# IoT_2015.net
KiCad netlist of a schematic drawn in EAGLE
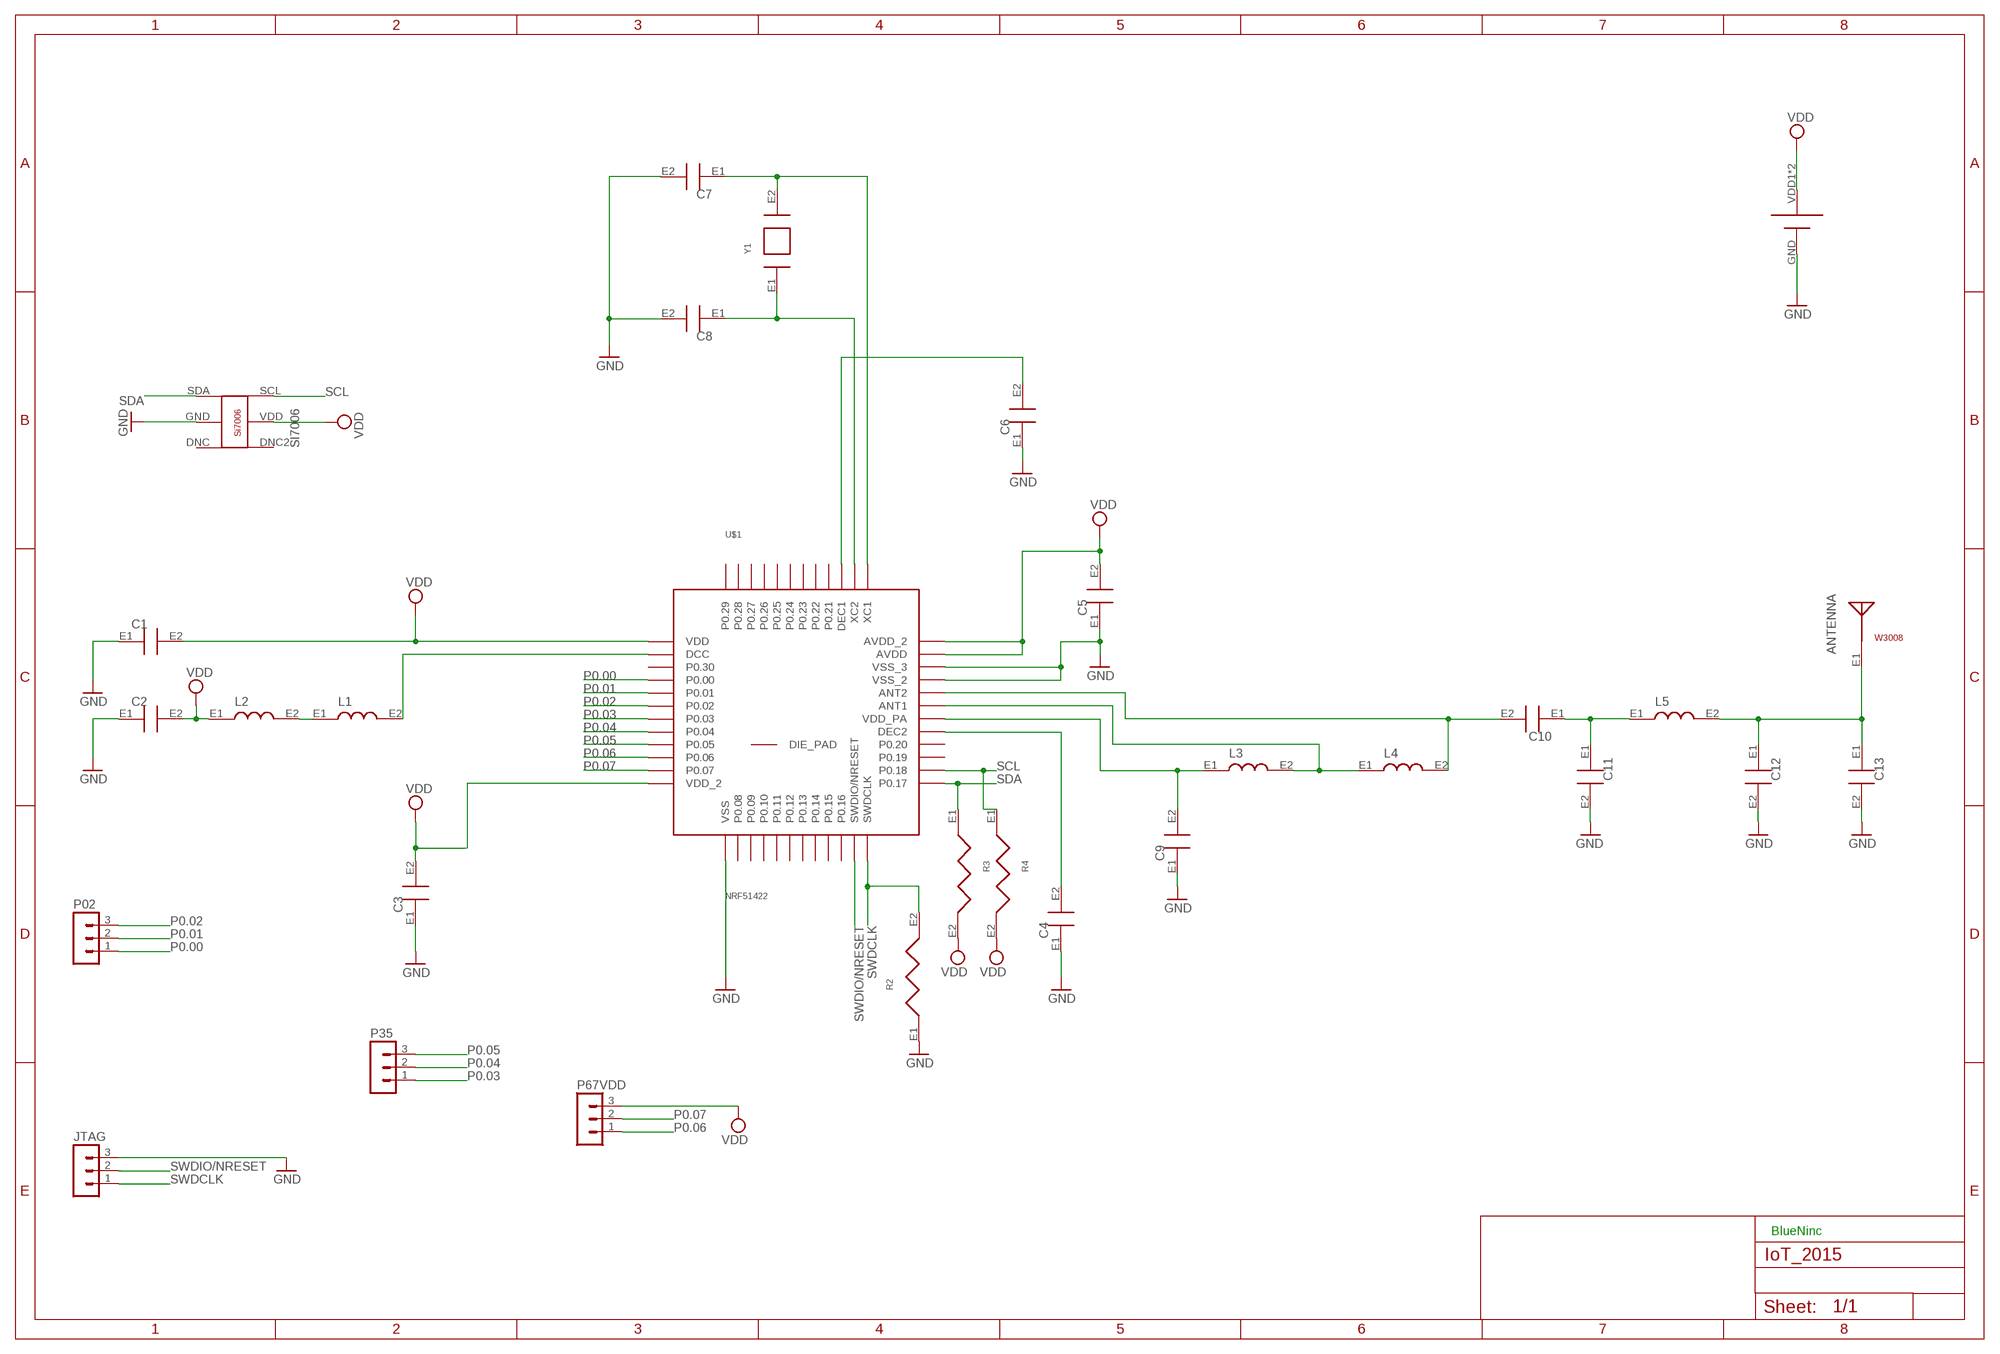
[diagram p0: schematic, sheet 1]

(export (version "E")
  (design (tool "Eeschema 10.0.6"))
  (components
    (comp (ref "ANTENNA")
      (value "W3008")
      (footprint "eagle-import:W3008")
      (libsource (lib "eagle-import") (part "W3008"))
    )
    (comp (ref "BATTERY")
      (value "BAT-HLD-001")
      (footprint "eagle-import:BAT-HLD-001")
      (libsource (lib "eagle-import") (part "BAT-HLD-001"))
    )
    (comp (ref "C1")
      (value "VJ1603_W1BC")
      (footprint "eagle-import:VJ1603_W1BC")
      (libsource (lib "eagle-import") (part "VJ1603_W1BC"))
    )
    (comp (ref "C2")
      (value "VJ1603_W1BC")
      (footprint "eagle-import:VJ1603_W1BC")
      (libsource (lib "eagle-import") (part "VJ1603_W1BC"))
    )
    (comp (ref "C3")
      (value "VJ1603_W1BC")
      (footprint "eagle-import:VJ1603_W1BC")
      (libsource (lib "eagle-import") (part "VJ1603_W1BC"))
    )
    (comp (ref "C4")
      (value "VJ1603_W1BC")
      (footprint "eagle-import:VJ1603_W1BC")
      (libsource (lib "eagle-import") (part "VJ1603_W1BC"))
    )
    (comp (ref "C5")
      (value "VJ1603_W1BC")
      (footprint "eagle-import:VJ1603_W1BC")
      (libsource (lib "eagle-import") (part "VJ1603_W1BC"))
    )
    (comp (ref "C6")
      (value "VJ1603_W1BC")
      (footprint "eagle-import:VJ1603_W1BC")
      (libsource (lib "eagle-import") (part "VJ1603_W1BC"))
    )
    (comp (ref "C7")
      (value "VJ1603_W1BC")
      (footprint "eagle-import:VJ1603_W1BC")
      (libsource (lib "eagle-import") (part "VJ1603_W1BC"))
    )
    (comp (ref "C8")
      (value "VJ1603_W1BC")
      (footprint "eagle-import:VJ1603_W1BC")
      (libsource (lib "eagle-import") (part "VJ1603_W1BC"))
    )
    (comp (ref "C9")
      (value "VJ1603_W1BC")
      (footprint "eagle-import:VJ1603_W1BC")
      (libsource (lib "eagle-import") (part "VJ1603_W1BC"))
    )
    (comp (ref "C10")
      (value "VJ1603_W1BC")
      (footprint "eagle-import:VJ1603_W1BC")
      (libsource (lib "eagle-import") (part "VJ1603_W1BC"))
    )
    (comp (ref "C11")
      (value "VJ1603_W1BC")
      (footprint "eagle-import:VJ1603_W1BC")
      (libsource (lib "eagle-import") (part "VJ1603_W1BC"))
    )
    (comp (ref "C12")
      (value "VJ1603_W1BC")
      (footprint "eagle-import:VJ1603_W1BC")
      (libsource (lib "eagle-import") (part "VJ1603_W1BC"))
    )
    (comp (ref "C13")
      (value "VJ1603_W1BC")
      (footprint "eagle-import:VJ1603_W1BC")
      (libsource (lib "eagle-import") (part "VJ1603_W1BC"))
    )
    (comp (ref "JTAG")
      (value "MA03-1")
      (footprint "eagle-import:MA03-1")
      (libsource (lib "eagle-import") (part "MA03-1"))
    )
    (comp (ref "L1")
      (value "JTI_CAT_2012_INDUCTORS_CHIP-242427")
      (footprint "eagle-import:JTI_CAT_2012_INDUCTORS_CHIP-242427")
      (libsource (lib "eagle-import") (part "JTI_CAT_2012_INDUCTORS_CHIP-242427"))
    )
    (comp (ref "L2")
      (value "JTI_CAT_2012_INDUCTORS_CHIP-242427")
      (footprint "eagle-import:JTI_CAT_2012_INDUCTORS_CHIP-242427")
      (libsource (lib "eagle-import") (part "JTI_CAT_2012_INDUCTORS_CHIP-242427"))
    )
    (comp (ref "L3")
      (value "JTI_CAT_2012_INDUCTORS_CHIP-242427")
      (footprint "eagle-import:JTI_CAT_2012_INDUCTORS_CHIP-242427")
      (libsource (lib "eagle-import") (part "JTI_CAT_2012_INDUCTORS_CHIP-242427"))
    )
    (comp (ref "L4")
      (value "JTI_CAT_2012_INDUCTORS_CHIP-242427")
      (footprint "eagle-import:JTI_CAT_2012_INDUCTORS_CHIP-242427")
      (libsource (lib "eagle-import") (part "JTI_CAT_2012_INDUCTORS_CHIP-242427"))
    )
    (comp (ref "L5")
      (value "JTI_CAT_2012_INDUCTORS_CHIP-242427")
      (footprint "eagle-import:JTI_CAT_2012_INDUCTORS_CHIP-242427")
      (libsource (lib "eagle-import") (part "JTI_CAT_2012_INDUCTORS_CHIP-242427"))
    )
    (comp (ref "P02")
      (value "MA03-1")
      (footprint "eagle-import:MA03-1")
      (libsource (lib "eagle-import") (part "MA03-1"))
    )
    (comp (ref "P35")
      (value "MA03-1")
      (footprint "eagle-import:MA03-1")
      (libsource (lib "eagle-import") (part "MA03-1"))
    )
    (comp (ref "P67VDD")
      (value "MA03-1")
      (footprint "eagle-import:MA03-1")
      (libsource (lib "eagle-import") (part "MA03-1"))
    )
    (comp (ref "R2")
      (value "ERJ-3GEYJ103V")
      (footprint "eagle-import:ERJ-3GEYJ103V")
      (libsource (lib "eagle-import") (part "ERJ-3GEYJ103V"))
    )
    (comp (ref "R3")
      (value "ERJ-3GEYJ103V")
      (footprint "eagle-import:ERJ-3GEYJ103V")
      (libsource (lib "eagle-import") (part "ERJ-3GEYJ103V"))
    )
    (comp (ref "R4")
      (value "ERJ-3GEYJ103V")
      (footprint "eagle-import:ERJ-3GEYJ103V")
      (libsource (lib "eagle-import") (part "ERJ-3GEYJ103V"))
    )
    (comp (ref "SI7006")
      (value "SI7006-A20-IM")
      (footprint "eagle-import:SI7006-A20-IM")
      (libsource (lib "eagle-import") (part "SI7006-A20-IM"))
    )
    (comp (ref "U$1")
      (value "NRF51422")
      (footprint "eagle-import:QFN48")
      (libsource (lib "eagle-import") (part "NRF51422"))
    )
    (comp (ref "Y1")
      (value "ABLS-16.000MHZ-B4-T")
      (footprint "eagle-import:ABLS-16.000MHZ-B4-T")
      (libsource (lib "eagle-import") (part "ABLS-16.000MHZ-B4-T"))
    )
  )
  (nets
    (net (code "1") (name "/P0.00") (class "Default")
      (node (ref "P02") (pin "1") (pinfunction "1_1") (pintype "passive"))
      (node (ref "U$1") (pin "4") (pinfunction "P0.00_4") (pintype "bidirectional"))
    )
    (net (code "2") (name "/P0.01") (class "Default")
      (node (ref "P02") (pin "2") (pinfunction "2_2") (pintype "passive"))
      (node (ref "U$1") (pin "5") (pinfunction "P0.01_5") (pintype "bidirectional"))
    )
    (net (code "3") (name "/P0.02") (class "Default")
      (node (ref "P02") (pin "3") (pinfunction "3_3") (pintype "passive"))
      (node (ref "U$1") (pin "6") (pinfunction "P0.02_6") (pintype "bidirectional"))
    )
    (net (code "4") (name "/P0.03") (class "Default")
      (node (ref "P35") (pin "1") (pinfunction "1_1") (pintype "passive"))
      (node (ref "U$1") (pin "7") (pinfunction "P0.03_7") (pintype "bidirectional"))
    )
    (net (code "5") (name "/P0.04") (class "Default")
      (node (ref "P35") (pin "2") (pinfunction "2_2") (pintype "passive"))
      (node (ref "U$1") (pin "8") (pinfunction "P0.04_8") (pintype "bidirectional"))
    )
    (net (code "6") (name "/P0.05") (class "Default")
      (node (ref "P35") (pin "3") (pinfunction "3_3") (pintype "passive"))
      (node (ref "U$1") (pin "9") (pinfunction "P0.05_9") (pintype "bidirectional"))
    )
    (net (code "7") (name "/P0.06") (class "Default")
      (node (ref "P67VDD") (pin "1") (pinfunction "1_1") (pintype "passive"))
      (node (ref "U$1") (pin "10") (pinfunction "P0.06_10") (pintype "bidirectional"))
    )
    (net (code "8") (name "/P0.07") (class "Default")
      (node (ref "P67VDD") (pin "2") (pinfunction "2_2") (pintype "passive"))
      (node (ref "U$1") (pin "11") (pinfunction "P0.07_11") (pintype "bidirectional"))
    )
    (net (code "9") (name "/SCL") (class "Default")
      (node (ref "R4") (pin "E1") (pinfunction "E1_E1") (pintype "bidirectional"))
      (node (ref "SI7006") (pin "SCL") (pinfunction "SCL_SCL") (pintype "bidirectional"))
      (node (ref "U$1") (pin "26") (pinfunction "P0.18_26") (pintype "bidirectional"))
    )
    (net (code "10") (name "/SDA") (class "Default")
      (node (ref "R3") (pin "E1") (pinfunction "E1_E1") (pintype "bidirectional"))
      (node (ref "SI7006") (pin "SDA") (pinfunction "SDA_SDA") (pintype "bidirectional"))
      (node (ref "U$1") (pin "25") (pinfunction "P0.17_25") (pintype "bidirectional"))
    )
    (net (code "11") (name "/SWDCLK") (class "Default")
      (node (ref "JTAG") (pin "1") (pinfunction "1_1") (pintype "passive"))
      (node (ref "R2") (pin "E2") (pinfunction "E2_E2") (pintype "bidirectional"))
      (node (ref "U$1") (pin "24") (pinfunction "SWDCLK_24") (pintype "bidirectional"))
    )
    (net (code "12") (name "/SWDIO{slash}NRESET") (class "Default")
      (node (ref "JTAG") (pin "2") (pinfunction "2_2") (pintype "passive"))
      (node (ref "U$1") (pin "23") (pinfunction "SWDIO/NRESET_23") (pintype "bidirectional"))
    )
    (net (code "13") (name "GND") (class "Default")
      (node (ref "BATTERY") (pin "GND") (pinfunction "GND_GND") (pintype "bidirectional"))
      (node (ref "C1") (pin "E1") (pinfunction "E1_E1") (pintype "bidirectional"))
      (node (ref "C11") (pin "E2") (pinfunction "E2_E2") (pintype "bidirectional"))
      (node (ref "C12") (pin "E2") (pinfunction "E2_E2") (pintype "bidirectional"))
      (node (ref "C13") (pin "E2") (pinfunction "E2_E2") (pintype "bidirectional"))
      (node (ref "C2") (pin "E1") (pinfunction "E1_E1") (pintype "bidirectional"))
      (node (ref "C3") (pin "E1") (pinfunction "E1_E1") (pintype "bidirectional"))
      (node (ref "C4") (pin "E1") (pinfunction "E1_E1") (pintype "bidirectional"))
      (node (ref "C5") (pin "E1") (pinfunction "E1_E1") (pintype "bidirectional"))
      (node (ref "C6") (pin "E1") (pinfunction "E1_E1") (pintype "bidirectional"))
      (node (ref "C7") (pin "E2") (pinfunction "E2_E2") (pintype "bidirectional"))
      (node (ref "C8") (pin "E2") (pinfunction "E2_E2") (pintype "bidirectional"))
      (node (ref "C9") (pin "E1") (pinfunction "E1_E1") (pintype "bidirectional"))
      (node (ref "JTAG") (pin "3") (pinfunction "3_3") (pintype "passive"))
      (node (ref "R2") (pin "E1") (pinfunction "E1_E1") (pintype "bidirectional"))
      (node (ref "SI7006") (pin "GND") (pinfunction "GND_GND") (pintype "bidirectional"))
      (node (ref "U$1") (pin "13") (pinfunction "VSS_13") (pintype "bidirectional"))
      (node (ref "U$1") (pin "33") (pinfunction "VSS_2_33") (pintype "bidirectional"))
      (node (ref "U$1") (pin "34") (pinfunction "VSS_3_34") (pintype "bidirectional"))
    )
    (net (code "14") (name "Net-(ANTENNA-PadE1)") (class "Default")
      (node (ref "ANTENNA") (pin "E1") (pinfunction "E1_E1") (pintype "bidirectional"))
      (node (ref "C12") (pin "E1") (pinfunction "E1_E1") (pintype "bidirectional"))
      (node (ref "C13") (pin "E1") (pinfunction "E1_E1") (pintype "bidirectional"))
      (node (ref "L5") (pin "E2") (pinfunction "E2_E2") (pintype "bidirectional"))
    )
    (net (code "15") (name "Net-(C10-PadE1)") (class "Default")
      (node (ref "C10") (pin "E1") (pinfunction "E1_E1") (pintype "bidirectional"))
      (node (ref "C11") (pin "E1") (pinfunction "E1_E1") (pintype "bidirectional"))
      (node (ref "L5") (pin "E1") (pinfunction "E1_E1") (pintype "bidirectional"))
    )
    (net (code "16") (name "Net-(L1-PadE1)") (class "Default")
      (node (ref "L1") (pin "E1") (pinfunction "E1_E1") (pintype "bidirectional"))
      (node (ref "L2") (pin "E2") (pinfunction "E2_E2") (pintype "bidirectional"))
    )
    (net (code "17") (name "Net-(U$1-ANT1)") (class "Default")
      (node (ref "L3") (pin "E2") (pinfunction "E2_E2") (pintype "bidirectional"))
      (node (ref "L4") (pin "E1") (pinfunction "E1_E1") (pintype "bidirectional"))
      (node (ref "U$1") (pin "31") (pinfunction "ANT1_31") (pintype "bidirectional"))
    )
    (net (code "18") (name "Net-(U$1-ANT2)") (class "Default")
      (node (ref "C10") (pin "E2") (pinfunction "E2_E2") (pintype "bidirectional"))
      (node (ref "L4") (pin "E2") (pinfunction "E2_E2") (pintype "bidirectional"))
      (node (ref "U$1") (pin "32") (pinfunction "ANT2_32") (pintype "bidirectional"))
    )
    (net (code "19") (name "Net-(U$1-DCC)") (class "Default")
      (node (ref "L1") (pin "E2") (pinfunction "E2_E2") (pintype "bidirectional"))
      (node (ref "U$1") (pin "2") (pinfunction "DCC_2") (pintype "bidirectional"))
    )
    (net (code "20") (name "Net-(U$1-DEC1)") (class "Default")
      (node (ref "C6") (pin "E2") (pinfunction "E2_E2") (pintype "bidirectional"))
      (node (ref "U$1") (pin "39") (pinfunction "DEC1_39") (pintype "bidirectional"))
    )
    (net (code "21") (name "Net-(U$1-DEC2)") (class "Default")
      (node (ref "C4") (pin "E2") (pinfunction "E2_E2") (pintype "bidirectional"))
      (node (ref "U$1") (pin "29") (pinfunction "DEC2_29") (pintype "bidirectional"))
    )
    (net (code "22") (name "Net-(U$1-VDD_PA)") (class "Default")
      (node (ref "C9") (pin "E2") (pinfunction "E2_E2") (pintype "bidirectional"))
      (node (ref "L3") (pin "E1") (pinfunction "E1_E1") (pintype "bidirectional"))
      (node (ref "U$1") (pin "30") (pinfunction "VDD_PA_30") (pintype "bidirectional"))
    )
    (net (code "23") (name "Net-(U$1-XC1)") (class "Default")
      (node (ref "C7") (pin "E1") (pinfunction "E1_E1") (pintype "bidirectional"))
      (node (ref "U$1") (pin "37") (pinfunction "XC1_37") (pintype "bidirectional"))
      (node (ref "Y1") (pin "E2") (pinfunction "E2_E2") (pintype "bidirectional"))
    )
    (net (code "24") (name "Net-(U$1-XC2)") (class "Default")
      (node (ref "C8") (pin "E1") (pinfunction "E1_E1") (pintype "bidirectional"))
      (node (ref "U$1") (pin "38") (pinfunction "XC2_38") (pintype "bidirectional"))
      (node (ref "Y1") (pin "E1") (pinfunction "E1_E1") (pintype "bidirectional"))
    )
    (net (code "25") (name "VDD") (class "Default")
      (node (ref "BATTERY") (pin "VDD1") (pinfunction "VDD_VDD1") (pintype "bidirectional"))
      (node (ref "BATTERY") (pin "VDD2") (pinfunction "VDD_VDD2") (pintype "bidirectional"))
      (node (ref "C1") (pin "E2") (pinfunction "E2_E2") (pintype "bidirectional"))
      (node (ref "C2") (pin "E2") (pinfunction "E2_E2") (pintype "bidirectional"))
      (node (ref "C3") (pin "E2") (pinfunction "E2_E2") (pintype "bidirectional"))
      (node (ref "C5") (pin "E2") (pinfunction "E2_E2") (pintype "bidirectional"))
      (node (ref "L2") (pin "E1") (pinfunction "E1_E1") (pintype "bidirectional"))
      (node (ref "P67VDD") (pin "3") (pinfunction "3_3") (pintype "passive"))
      (node (ref "R3") (pin "E2") (pinfunction "E2_E2") (pintype "bidirectional"))
      (node (ref "R4") (pin "E2") (pinfunction "E2_E2") (pintype "bidirectional"))
      (node (ref "SI7006") (pin "VDD") (pinfunction "VDD_VDD") (pintype "bidirectional"))
      (node (ref "U$1") (pin "1") (pinfunction "VDD_1") (pintype "bidirectional"))
      (node (ref "U$1") (pin "12") (pinfunction "VDD_2_12") (pintype "bidirectional"))
      (node (ref "U$1") (pin "35") (pinfunction "AVDD_35") (pintype "bidirectional"))
      (node (ref "U$1") (pin "36") (pinfunction "AVDD_2_36") (pintype "bidirectional"))
    )
    (net (code "26") (name "unconnected-(SI7006-PadDNC)") (class "Default")
      (node (ref "SI7006") (pin "DNC") (pinfunction "DNC_DNC") (pintype "bidirectional"))
    )
    (net (code "27") (name "unconnected-(SI7006-PadDNC2)") (class "Default")
      (node (ref "SI7006") (pin "DNC2") (pinfunction "DNC2_DNC2") (pintype "bidirectional"))
    )
    (net (code "28") (name "unconnected-(U$1-DIE_PAD-PadGND)") (class "Default")
      (node (ref "U$1") (pin "GND") (pinfunction "DIE_PAD_GND") (pintype "bidirectional"))
    )
    (net (code "29") (name "unconnected-(U$1-P0.08-Pad14)") (class "Default")
      (node (ref "U$1") (pin "14") (pinfunction "P0.08_14") (pintype "bidirectional"))
    )
    (net (code "30") (name "unconnected-(U$1-P0.09-Pad15)") (class "Default")
      (node (ref "U$1") (pin "15") (pinfunction "P0.09_15") (pintype "bidirectional"))
    )
    (net (code "31") (name "unconnected-(U$1-P0.10-Pad16)") (class "Default")
      (node (ref "U$1") (pin "16") (pinfunction "P0.10_16") (pintype "bidirectional"))
    )
    (net (code "32") (name "unconnected-(U$1-P0.11-Pad17)") (class "Default")
      (node (ref "U$1") (pin "17") (pinfunction "P0.11_17") (pintype "bidirectional"))
    )
    (net (code "33") (name "unconnected-(U$1-P0.12-Pad18)") (class "Default")
      (node (ref "U$1") (pin "18") (pinfunction "P0.12_18") (pintype "bidirectional"))
    )
    (net (code "34") (name "unconnected-(U$1-P0.13-Pad19)") (class "Default")
      (node (ref "U$1") (pin "19") (pinfunction "P0.13_19") (pintype "bidirectional"))
    )
    (net (code "35") (name "unconnected-(U$1-P0.14-Pad20)") (class "Default")
      (node (ref "U$1") (pin "20") (pinfunction "P0.14_20") (pintype "bidirectional"))
    )
    (net (code "36") (name "unconnected-(U$1-P0.15-Pad21)") (class "Default")
      (node (ref "U$1") (pin "21") (pinfunction "P0.15_21") (pintype "bidirectional"))
    )
    (net (code "37") (name "unconnected-(U$1-P0.16-Pad22)") (class "Default")
      (node (ref "U$1") (pin "22") (pinfunction "P0.16_22") (pintype "bidirectional"))
    )
    (net (code "38") (name "unconnected-(U$1-P0.19-Pad27)") (class "Default")
      (node (ref "U$1") (pin "27") (pinfunction "P0.19_27") (pintype "bidirectional"))
    )
    (net (code "39") (name "unconnected-(U$1-P0.20-Pad28)") (class "Default")
      (node (ref "U$1") (pin "28") (pinfunction "P0.20_28") (pintype "bidirectional"))
    )
    (net (code "40") (name "unconnected-(U$1-P0.21-Pad40)") (class "Default")
      (node (ref "U$1") (pin "40") (pinfunction "P0.21_40") (pintype "bidirectional"))
    )
    (net (code "41") (name "unconnected-(U$1-P0.22-Pad41)") (class "Default")
      (node (ref "U$1") (pin "41") (pinfunction "P0.22_41") (pintype "bidirectional"))
    )
    (net (code "42") (name "unconnected-(U$1-P0.23-Pad42)") (class "Default")
      (node (ref "U$1") (pin "42") (pinfunction "P0.23_42") (pintype "bidirectional"))
    )
    (net (code "43") (name "unconnected-(U$1-P0.24-Pad43)") (class "Default")
      (node (ref "U$1") (pin "43") (pinfunction "P0.24_43") (pintype "bidirectional"))
    )
    (net (code "44") (name "unconnected-(U$1-P0.25-Pad44)") (class "Default")
      (node (ref "U$1") (pin "44") (pinfunction "P0.25_44") (pintype "bidirectional"))
    )
    (net (code "45") (name "unconnected-(U$1-P0.26-Pad45)") (class "Default")
      (node (ref "U$1") (pin "45") (pinfunction "P0.26_45") (pintype "bidirectional"))
    )
    (net (code "46") (name "unconnected-(U$1-P0.27-Pad46)") (class "Default")
      (node (ref "U$1") (pin "46") (pinfunction "P0.27_46") (pintype "bidirectional"))
    )
    (net (code "47") (name "unconnected-(U$1-P0.28-Pad47)") (class "Default")
      (node (ref "U$1") (pin "47") (pinfunction "P0.28_47") (pintype "bidirectional"))
    )
    (net (code "48") (name "unconnected-(U$1-P0.29-Pad48)") (class "Default")
      (node (ref "U$1") (pin "48") (pinfunction "P0.29_48") (pintype "bidirectional"))
    )
    (net (code "49") (name "unconnected-(U$1-P0.30-Pad3)") (class "Default")
      (node (ref "U$1") (pin "3") (pinfunction "P0.30_3") (pintype "bidirectional"))
    )
  )
)
